# A4989.net
KiCad netlist of a schematic drawn in EAGLE
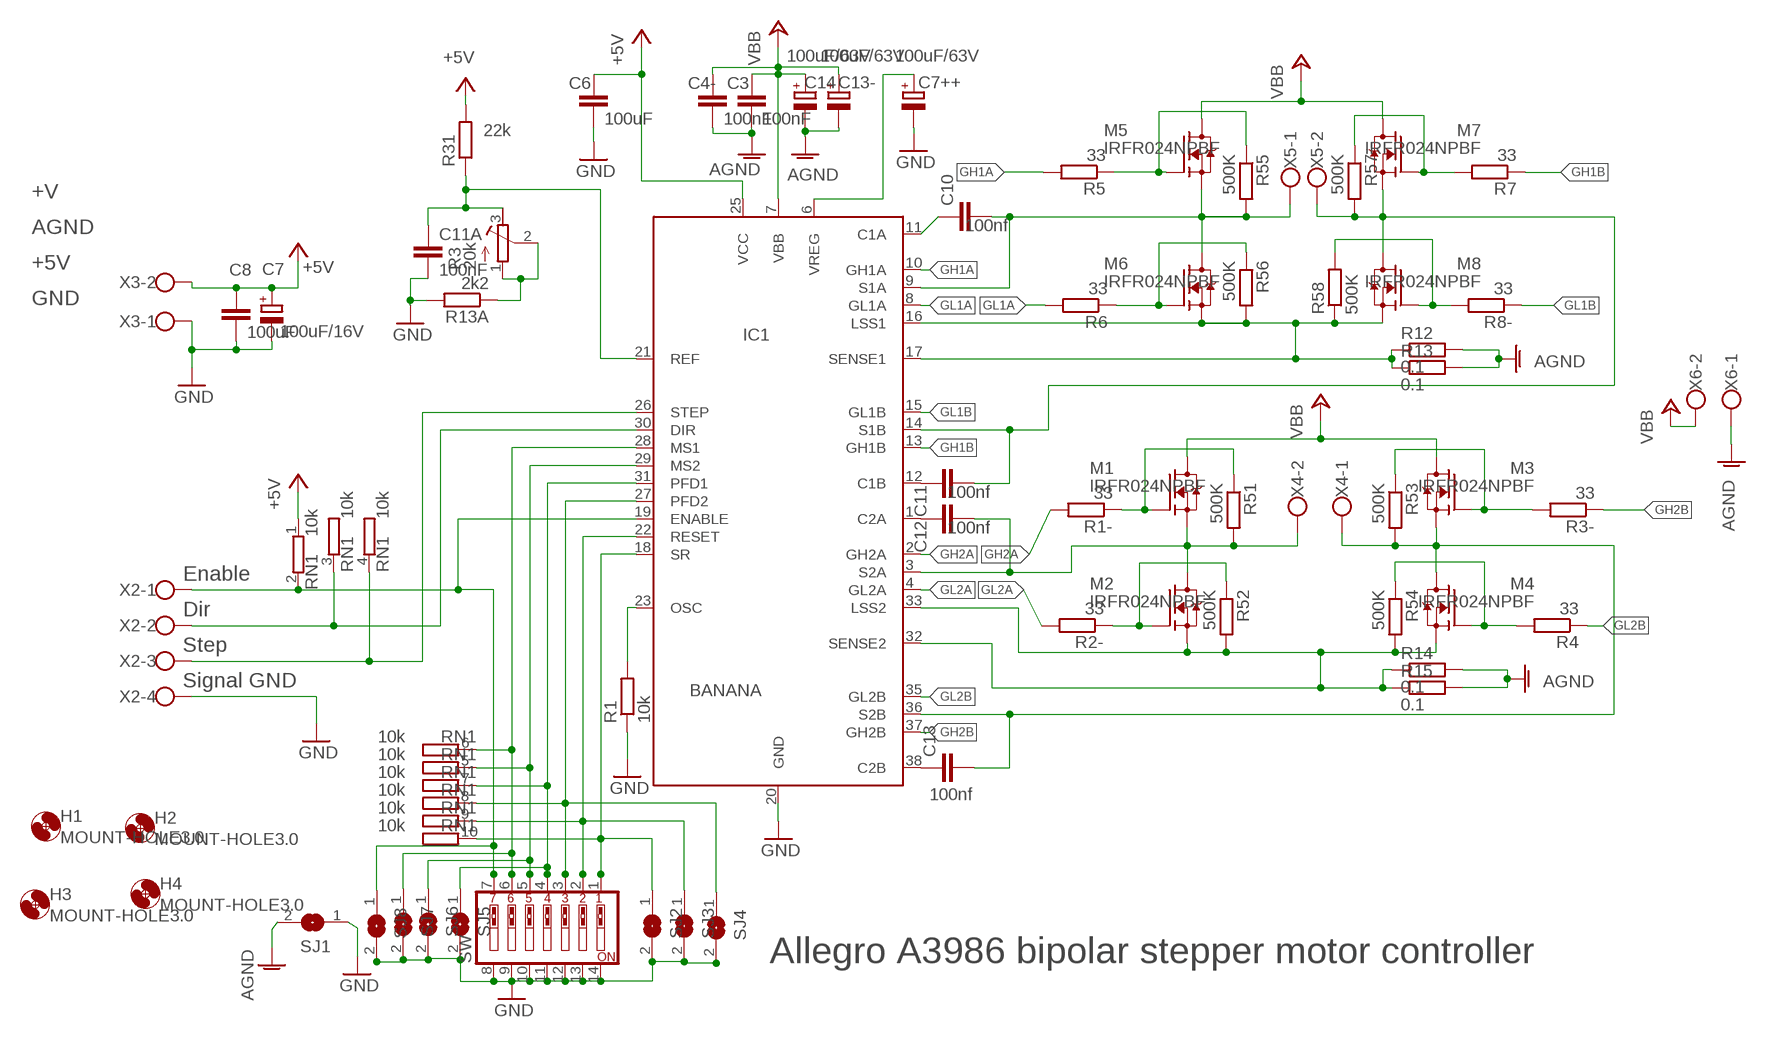
[diagram p0: schematic, sheet 1]

(export (version "E")
  (design (tool "Eeschema 10.0.6"))
  (components
    (comp (ref "C3")
      (value "100nF")
      (footprint "eagle-import:C0805")
      (libsource (lib "eagle-import") (part "C-EUC0805"))
    )
    (comp (ref "C4-")
      (value "100nF")
      (footprint "eagle-import:C0805")
      (libsource (lib "eagle-import") (part "C-EUC0805"))
    )
    (comp (ref "C6")
      (value "100uF")
      (footprint "eagle-import:C0805")
      (libsource (lib "eagle-import") (part "C-EUC0805"))
    )
    (comp (ref "C7")
      (value "100uF/16V")
      (footprint "eagle-import:E5-10,5")
      (libsource (lib "eagle-import") (part "CPOL-EUE5-10.5"))
    )
    (comp (ref "C7++")
      (value "100uF/63V")
      (footprint "eagle-import:E2-5")
      (libsource (lib "eagle-import") (part "resistor_CPOL-EUE2-5"))
    )
    (comp (ref "C8")
      (value "100uF")
      (footprint "eagle-import:C0805")
      (libsource (lib "eagle-import") (part "C-EUC0805"))
    )
    (comp (ref "C10")
      (value "100nf")
      (footprint "eagle-import:C0805")
      (libsource (lib "eagle-import") (part "C-EUC0805"))
    )
    (comp (ref "C11")
      (value "100nf")
      (footprint "eagle-import:C0805")
      (libsource (lib "eagle-import") (part "C-EUC0805"))
    )
    (comp (ref "C11A")
      (value "100nF")
      (footprint "eagle-import:C0805")
      (libsource (lib "eagle-import") (part "C-EUC0805"))
    )
    (comp (ref "C12")
      (value "100nf")
      (footprint "eagle-import:C0805")
      (libsource (lib "eagle-import") (part "C-EUC0805"))
    )
    (comp (ref "C13")
      (value "100nf")
      (footprint "eagle-import:C0805")
      (libsource (lib "eagle-import") (part "C-EUC0805"))
    )
    (comp (ref "C13-")
      (value "100uF/63V")
      (footprint "eagle-import:E5-10,5")
      (libsource (lib "eagle-import") (part "resistor_CPOL-EUE5-10.5"))
    )
    (comp (ref "C14")
      (value "100uF/63V")
      (footprint "eagle-import:E5-10,5")
      (libsource (lib "eagle-import") (part "resistor_CPOL-EUE5-10.5"))
    )
    (comp (ref "H1")
      (value "MOUNT-HOLE3.0")
      (footprint "eagle-import:3,0")
      (libsource (lib "eagle-import") (part "MOUNT-HOLE3.0"))
    )
    (comp (ref "H2")
      (value "MOUNT-HOLE3.0")
      (footprint "eagle-import:3,0")
      (libsource (lib "eagle-import") (part "MOUNT-HOLE3.0"))
    )
    (comp (ref "H3")
      (value "MOUNT-HOLE3.0")
      (footprint "eagle-import:3,0")
      (libsource (lib "eagle-import") (part "MOUNT-HOLE3.0"))
    )
    (comp (ref "H4")
      (value "MOUNT-HOLE3.0")
      (footprint "eagle-import:3,0")
      (libsource (lib "eagle-import") (part "MOUNT-HOLE3.0"))
    )
    (comp (ref "IC1")
      (value "BANANA")
      (footprint "eagle-import:TSSOP38")
      (libsource (lib "eagle-import") (part "A3986"))
    )
    (comp (ref "M1")
      (value "IRFR024NPBF")
      (footprint "eagle-import:DPAK")
      (libsource (lib "eagle-import") (part "IRFR024NPBF"))
    )
    (comp (ref "M2")
      (value "IRFR024NPBF")
      (footprint "eagle-import:DPAK")
      (libsource (lib "eagle-import") (part "IRFR024NPBF"))
    )
    (comp (ref "M3")
      (value "IRFR024NPBF")
      (footprint "eagle-import:DPAK")
      (libsource (lib "eagle-import") (part "IRFR024NPBF"))
    )
    (comp (ref "M4")
      (value "IRFR024NPBF")
      (footprint "eagle-import:DPAK")
      (libsource (lib "eagle-import") (part "IRFR024NPBF"))
    )
    (comp (ref "M5")
      (value "IRFR024NPBF")
      (footprint "eagle-import:DPAK")
      (libsource (lib "eagle-import") (part "IRFR024NPBF"))
    )
    (comp (ref "M6")
      (value "IRFR024NPBF")
      (footprint "eagle-import:DPAK")
      (libsource (lib "eagle-import") (part "IRFR024NPBF"))
    )
    (comp (ref "M7")
      (value "IRFR024NPBF")
      (footprint "eagle-import:DPAK")
      (libsource (lib "eagle-import") (part "IRFR024NPBF"))
    )
    (comp (ref "M8")
      (value "IRFR024NPBF")
      (footprint "eagle-import:DPAK")
      (libsource (lib "eagle-import") (part "IRFR024NPBF"))
    )
    (comp (ref "R1")
      (value "10k")
      (footprint "eagle-import:M0805")
      (libsource (lib "eagle-import") (part "R-EU_M0805"))
    )
    (comp (ref "R1-")
      (value "33")
      (footprint "eagle-import:R0805")
      (libsource (lib "eagle-import") (part "R-EU_R0805"))
    )
    (comp (ref "R2-")
      (value "33")
      (footprint "eagle-import:R0805")
      (libsource (lib "eagle-import") (part "R-EU_R0805"))
    )
    (comp (ref "R3")
      (value "20k")
      (footprint "eagle-import:RTRIM64W")
      (libsource (lib "eagle-import") (part "R-TRIMM64W"))
    )
    (comp (ref "R3-")
      (value "33")
      (footprint "eagle-import:R0805")
      (libsource (lib "eagle-import") (part "R-EU_R0805"))
    )
    (comp (ref "R4")
      (value "33")
      (footprint "eagle-import:R0805")
      (libsource (lib "eagle-import") (part "R-EU_R0805"))
    )
    (comp (ref "R5")
      (value "33")
      (footprint "eagle-import:R0805")
      (libsource (lib "eagle-import") (part "R-EU_R0805"))
    )
    (comp (ref "R6")
      (value "33")
      (footprint "eagle-import:R0805")
      (libsource (lib "eagle-import") (part "R-EU_R0805"))
    )
    (comp (ref "R7")
      (value "33")
      (footprint "eagle-import:R0805")
      (libsource (lib "eagle-import") (part "R-EU_R0805"))
    )
    (comp (ref "R8-")
      (value "33")
      (footprint "eagle-import:R0805")
      (libsource (lib "eagle-import") (part "R-EU_R0805"))
    )
    (comp (ref "R12")
      (value "0.1")
      (footprint "eagle-import:R2512")
      (libsource (lib "eagle-import") (part "R-EU_R2512"))
    )
    (comp (ref "R13")
      (value "0.1")
      (footprint "eagle-import:R2512")
      (libsource (lib "eagle-import") (part "R-EU_R2512"))
    )
    (comp (ref "R13A")
      (value "2k2")
      (footprint "eagle-import:M0805")
      (libsource (lib "eagle-import") (part "R-EU_M0805"))
    )
    (comp (ref "R14")
      (value "0.1")
      (footprint "eagle-import:R2512")
      (libsource (lib "eagle-import") (part "R-EU_R2512"))
    )
    (comp (ref "R15")
      (value "0.1")
      (footprint "eagle-import:R2512")
      (libsource (lib "eagle-import") (part "R-EU_R2512"))
    )
    (comp (ref "R31")
      (value "22k")
      (footprint "eagle-import:M0805")
      (libsource (lib "eagle-import") (part "R-EU_M0805"))
    )
    (comp (ref "R51")
      (value "500K")
      (footprint "eagle-import:R0805")
      (libsource (lib "eagle-import") (part "R-EU_R0805"))
    )
    (comp (ref "R52")
      (value "500K")
      (footprint "eagle-import:R0805")
      (libsource (lib "eagle-import") (part "R-EU_R0805"))
    )
    (comp (ref "R53")
      (value "500K")
      (footprint "eagle-import:R0805")
      (libsource (lib "eagle-import") (part "R-EU_R0805"))
    )
    (comp (ref "R54")
      (value "500K")
      (footprint "eagle-import:R0805")
      (libsource (lib "eagle-import") (part "R-EU_R0805"))
    )
    (comp (ref "R55")
      (value "500K")
      (footprint "eagle-import:R0805")
      (libsource (lib "eagle-import") (part "R-EU_R0805"))
    )
    (comp (ref "R56")
      (value "500K")
      (footprint "eagle-import:R0805")
      (libsource (lib "eagle-import") (part "R-EU_R0805"))
    )
    (comp (ref "R57")
      (value "500K")
      (footprint "eagle-import:R0805")
      (libsource (lib "eagle-import") (part "R-EU_R0805"))
    )
    (comp (ref "R58")
      (value "500K")
      (footprint "eagle-import:R0805")
      (libsource (lib "eagle-import") (part "R-EU_R0805"))
    )
    (comp (ref "RN1")
      (value "10k")
      (footprint "eagle-import:SIL10")
      (libsource (lib "eagle-import") (part "GE09RP"))
    )
    (comp (ref "SJ1") (value "SJ") (footprint "eagle-import:SJ") (libsource (lib "eagle-import") (part "SJ")))
    (comp (ref "SJ2") (value "SJ") (footprint "eagle-import:SJ") (libsource (lib "eagle-import") (part "SJ")))
    (comp (ref "SJ3") (value "SJ") (footprint "eagle-import:SJ") (libsource (lib "eagle-import") (part "SJ")))
    (comp (ref "SJ4") (value "SJ") (footprint "eagle-import:SJ") (libsource (lib "eagle-import") (part "SJ")))
    (comp (ref "SJ5") (value "SJ") (footprint "eagle-import:SJ") (libsource (lib "eagle-import") (part "SJ")))
    (comp (ref "SJ6") (value "SJ") (footprint "eagle-import:SJ") (libsource (lib "eagle-import") (part "SJ")))
    (comp (ref "SJ7") (value "SJ") (footprint "eagle-import:SJ") (libsource (lib "eagle-import") (part "SJ")))
    (comp (ref "SJ8") (value "SJ") (footprint "eagle-import:SJ") (libsource (lib "eagle-import") (part "SJ")))
    (comp (ref "SW")
      (value "SW_DIP-7")
      (footprint "eagle-import:EDG-07")
      (libsource (lib "eagle-import") (part "SW_DIP-7"))
    )
    (comp (ref "X2")
      (value "W237-4")
      (footprint "eagle-import:W237-4")
      (libsource (lib "eagle-import") (part "W237-4"))
    )
    (comp (ref "X3")
      (value "W237-102")
      (footprint "eagle-import:W237-102")
      (fields (field (name "MPN") "237-102"))
      (libsource (lib "eagle-import") (part "W237-102"))
    )
    (comp (ref "X4")
      (value "W237-102")
      (footprint "eagle-import:W237-102")
      (fields (field (name "MPN") "237-102"))
      (libsource (lib "eagle-import") (part "W237-102"))
    )
    (comp (ref "X5")
      (value "W237-102")
      (footprint "eagle-import:W237-102")
      (fields (field (name "MPN") "237-102"))
      (libsource (lib "eagle-import") (part "W237-102"))
    )
    (comp (ref "X6")
      (value "W237-102")
      (footprint "eagle-import:W237-102")
      (fields (field (name "MPN") "237-102"))
      (libsource (lib "eagle-import") (part "W237-102"))
    )
  )
  (nets
    (net (code "1") (name "+5V") (class "Default")
      (node (ref "C6") (pin "1") (pinfunction "1_1") (pintype "passive"))
      (node (ref "C7") (pin "+") (pinfunction "+_+") (pintype "passive"))
      (node (ref "C8") (pin "1") (pinfunction "1_1") (pintype "passive"))
      (node (ref "IC1") (pin "25") (pinfunction "VCC_25") (pintype "passive"))
      (node (ref "R31") (pin "2") (pinfunction "2_2") (pintype "passive"))
      (node (ref "RN1") (pin "1") (pinfunction "1_1") (pintype "passive"))
      (node (ref "X3") (pin "2") (pinfunction "KL_2") (pintype "passive"))
    )
    (net (code "2") (name "AGND") (class "Default")
      (node (ref "C13-") (pin "-") (pinfunction "-_-") (pintype "passive"))
      (node (ref "C14") (pin "-") (pinfunction "-_-") (pintype "passive"))
      (node (ref "C3") (pin "2") (pinfunction "2_2") (pintype "passive"))
      (node (ref "C4-") (pin "2") (pinfunction "2_2") (pintype "passive"))
      (node (ref "R12") (pin "2") (pinfunction "2_2") (pintype "passive"))
      (node (ref "R13") (pin "2") (pinfunction "2_2") (pintype "passive"))
      (node (ref "R14") (pin "2") (pinfunction "2_2") (pintype "passive"))
      (node (ref "R15") (pin "2") (pinfunction "2_2") (pintype "passive"))
      (node (ref "SJ1") (pin "2") (pinfunction "2_2") (pintype "passive"))
      (node (ref "X6") (pin "1") (pinfunction "KL_1") (pintype "passive"))
    )
    (net (code "3") (name "GH1A") (class "Default")
      (node (ref "IC1") (pin "10") (pinfunction "GH1A_10") (pintype "passive"))
      (node (ref "R5") (pin "2") (pinfunction "2_2") (pintype "passive"))
    )
    (net (code "4") (name "GH1B") (class "Default")
      (node (ref "IC1") (pin "13") (pinfunction "GH1B_13") (pintype "passive"))
      (node (ref "R7") (pin "1") (pinfunction "1_1") (pintype "passive"))
    )
    (net (code "5") (name "GH2A") (class "Default")
      (node (ref "IC1") (pin "2") (pinfunction "GH2A_2") (pintype "passive"))
      (node (ref "R1-") (pin "2") (pinfunction "2_2") (pintype "passive"))
    )
    (net (code "6") (name "GH2B") (class "Default")
      (node (ref "IC1") (pin "37") (pinfunction "GH2B_37") (pintype "passive"))
      (node (ref "R3-") (pin "1") (pinfunction "1_1") (pintype "passive"))
    )
    (net (code "7") (name "GL1A") (class "Default")
      (node (ref "IC1") (pin "8") (pinfunction "GL1A_8") (pintype "passive"))
      (node (ref "R6") (pin "2") (pinfunction "2_2") (pintype "passive"))
    )
    (net (code "8") (name "GL1B") (class "Default")
      (node (ref "IC1") (pin "15") (pinfunction "GL1B_15") (pintype "passive"))
      (node (ref "R8-") (pin "1") (pinfunction "1_1") (pintype "passive"))
    )
    (net (code "9") (name "GL2A") (class "Default")
      (node (ref "IC1") (pin "4") (pinfunction "GL2A_4") (pintype "passive"))
      (node (ref "R2-") (pin "2") (pinfunction "2_2") (pintype "passive"))
    )
    (net (code "10") (name "GL2B") (class "Default")
      (node (ref "IC1") (pin "35") (pinfunction "GL2B_35") (pintype "passive"))
      (node (ref "R4") (pin "1") (pinfunction "1_1") (pintype "passive"))
    )
    (net (code "11") (name "GND") (class "Default")
      (node (ref "C11A") (pin "2") (pinfunction "2_2") (pintype "passive"))
      (node (ref "C6") (pin "2") (pinfunction "2_2") (pintype "passive"))
      (node (ref "C7") (pin "-") (pinfunction "-_-") (pintype "passive"))
      (node (ref "C7++") (pin "-") (pinfunction "-_-") (pintype "passive"))
      (node (ref "C8") (pin "2") (pinfunction "2_2") (pintype "passive"))
      (node (ref "IC1") (pin "20") (pinfunction "GND_20") (pintype "passive"))
      (node (ref "R1") (pin "1") (pinfunction "1_1") (pintype "passive"))
      (node (ref "R13A") (pin "2") (pinfunction "2_2") (pintype "passive"))
      (node (ref "SJ1") (pin "1") (pinfunction "1_1") (pintype "passive"))
      (node (ref "SJ2") (pin "2") (pinfunction "2_2") (pintype "passive"))
      (node (ref "SJ3") (pin "2") (pinfunction "2_2") (pintype "passive"))
      (node (ref "SJ4") (pin "2") (pinfunction "2_2") (pintype "passive"))
      (node (ref "SJ5") (pin "2") (pinfunction "2_2") (pintype "passive"))
      (node (ref "SJ6") (pin "2") (pinfunction "2_2") (pintype "passive"))
      (node (ref "SJ7") (pin "2") (pinfunction "2_2") (pintype "passive"))
      (node (ref "SJ8") (pin "2") (pinfunction "2_2") (pintype "passive"))
      (node (ref "SW") (pin "10") (pinfunction "10_10") (pintype "passive"))
      (node (ref "SW") (pin "11") (pinfunction "11_11") (pintype "passive"))
      (node (ref "SW") (pin "12") (pinfunction "12_12") (pintype "passive"))
      (node (ref "SW") (pin "13") (pinfunction "13_13") (pintype "passive"))
      (node (ref "SW") (pin "14") (pinfunction "14_14") (pintype "passive"))
      (node (ref "SW") (pin "8") (pinfunction "8_8") (pintype "passive"))
      (node (ref "SW") (pin "9") (pinfunction "9_9") (pintype "passive"))
      (node (ref "X2") (pin "4") (pinfunction "KL_4") (pintype "passive"))
      (node (ref "X3") (pin "1") (pinfunction "KL_1") (pintype "passive"))
    )
    (net (code "12") (name "Net-(IC1-C1A)") (class "Default")
      (node (ref "C10") (pin "1") (pinfunction "1_1") (pintype "passive"))
      (node (ref "IC1") (pin "11") (pinfunction "C1A_11") (pintype "passive"))
    )
    (net (code "13") (name "Net-(IC1-C1B)") (class "Default")
      (node (ref "C11") (pin "1") (pinfunction "1_1") (pintype "passive"))
      (node (ref "IC1") (pin "12") (pinfunction "C1B_12") (pintype "passive"))
    )
    (net (code "14") (name "Net-(IC1-C2A)") (class "Default")
      (node (ref "C12") (pin "1") (pinfunction "1_1") (pintype "passive"))
      (node (ref "IC1") (pin "1") (pinfunction "C2A_1") (pintype "passive"))
    )
    (net (code "15") (name "Net-(IC1-C2B)") (class "Default")
      (node (ref "C13") (pin "1") (pinfunction "1_1") (pintype "passive"))
      (node (ref "IC1") (pin "38") (pinfunction "C2B_38") (pintype "passive"))
    )
    (net (code "16") (name "Net-(IC1-DIR)") (class "Default")
      (node (ref "IC1") (pin "30") (pinfunction "DIR_30") (pintype "passive"))
      (node (ref "RN1") (pin "3") (pinfunction "2_3") (pintype "passive"))
      (node (ref "X2") (pin "2") (pinfunction "KL_2") (pintype "passive"))
    )
    (net (code "17") (name "Net-(IC1-ENABLE)") (class "Default")
      (node (ref "IC1") (pin "19") (pinfunction "ENABLE_19") (pintype "passive"))
      (node (ref "RN1") (pin "2") (pinfunction "2_2") (pintype "passive"))
      (node (ref "SJ8") (pin "1") (pinfunction "1_1") (pintype "passive"))
      (node (ref "SW") (pin "7") (pinfunction "7_7") (pintype "passive"))
      (node (ref "X2") (pin "1") (pinfunction "KL_1") (pintype "passive"))
    )
    (net (code "18") (name "Net-(IC1-LSS1)") (class "Default")
      (node (ref "IC1") (pin "16") (pinfunction "LSS1_16") (pintype "passive"))
      (node (ref "IC1") (pin "17") (pinfunction "SENSE1_17") (pintype "passive"))
      (node (ref "M6") (pin "3") (pinfunction "S_3") (pintype "passive"))
      (node (ref "M8") (pin "3") (pinfunction "S_3") (pintype "passive"))
      (node (ref "R12") (pin "1") (pinfunction "1_1") (pintype "passive"))
      (node (ref "R13") (pin "1") (pinfunction "1_1") (pintype "passive"))
      (node (ref "R56") (pin "2") (pinfunction "2_2") (pintype "passive"))
      (node (ref "R58") (pin "1") (pinfunction "1_1") (pintype "passive"))
    )
    (net (code "19") (name "Net-(IC1-LSS2)") (class "Default")
      (node (ref "IC1") (pin "32") (pinfunction "SENSE2_32") (pintype "passive"))
      (node (ref "IC1") (pin "33") (pinfunction "LSS2_33") (pintype "passive"))
      (node (ref "M2") (pin "3") (pinfunction "S_3") (pintype "passive"))
      (node (ref "M4") (pin "3") (pinfunction "S_3") (pintype "passive"))
      (node (ref "R14") (pin "1") (pinfunction "1_1") (pintype "passive"))
      (node (ref "R15") (pin "1") (pinfunction "1_1") (pintype "passive"))
      (node (ref "R52") (pin "2") (pinfunction "2_2") (pintype "passive"))
      (node (ref "R54") (pin "2") (pinfunction "2_2") (pintype "passive"))
    )
    (net (code "20") (name "Net-(IC1-MS1)") (class "Default")
      (node (ref "IC1") (pin "28") (pinfunction "MS1_28") (pintype "passive"))
      (node (ref "RN1") (pin "6") (pinfunction "2_6") (pintype "passive"))
      (node (ref "SJ7") (pin "1") (pinfunction "1_1") (pintype "passive"))
      (node (ref "SW") (pin "6") (pinfunction "6_6") (pintype "passive"))
    )
    (net (code "21") (name "Net-(IC1-MS2)") (class "Default")
      (node (ref "IC1") (pin "29") (pinfunction "MS2_29") (pintype "passive"))
      (node (ref "RN1") (pin "5") (pinfunction "2_5") (pintype "passive"))
      (node (ref "SJ6") (pin "1") (pinfunction "1_1") (pintype "passive"))
      (node (ref "SW") (pin "5") (pinfunction "5_5") (pintype "passive"))
    )
    (net (code "22") (name "Net-(IC1-OSC)") (class "Default")
      (node (ref "IC1") (pin "23") (pinfunction "OSC_23") (pintype "passive"))
      (node (ref "R1") (pin "2") (pinfunction "2_2") (pintype "passive"))
    )
    (net (code "23") (name "Net-(IC1-PFD1)") (class "Default")
      (node (ref "IC1") (pin "31") (pinfunction "PFD1_31") (pintype "passive"))
      (node (ref "RN1") (pin "7") (pinfunction "2_7") (pintype "passive"))
      (node (ref "SJ5") (pin "1") (pinfunction "1_1") (pintype "passive"))
      (node (ref "SW") (pin "4") (pinfunction "4_4") (pintype "passive"))
    )
    (net (code "24") (name "Net-(IC1-PFD2)") (class "Default")
      (node (ref "IC1") (pin "27") (pinfunction "PFD2_27") (pintype "passive"))
      (node (ref "RN1") (pin "8") (pinfunction "2_8") (pintype "passive"))
      (node (ref "SJ4") (pin "1") (pinfunction "1_1") (pintype "passive"))
      (node (ref "SW") (pin "3") (pinfunction "3_3") (pintype "passive"))
    )
    (net (code "25") (name "Net-(IC1-REF)") (class "Default")
      (node (ref "C11A") (pin "1") (pinfunction "1_1") (pintype "passive"))
      (node (ref "IC1") (pin "21") (pinfunction "REF_21") (pintype "passive"))
      (node (ref "R3") (pin "3") (pinfunction "A_3") (pintype "passive"))
      (node (ref "R31") (pin "1") (pinfunction "1_1") (pintype "passive"))
    )
    (net (code "26") (name "Net-(IC1-RESET)") (class "Default")
      (node (ref "IC1") (pin "22") (pinfunction "RESET_22") (pintype "passive"))
      (node (ref "RN1") (pin "9") (pinfunction "2_9") (pintype "passive"))
      (node (ref "SJ3") (pin "1") (pinfunction "1_1") (pintype "passive"))
      (node (ref "SW") (pin "2") (pinfunction "2_2") (pintype "passive"))
    )
    (net (code "27") (name "Net-(IC1-S1A)") (class "Default")
      (node (ref "C10") (pin "2") (pinfunction "2_2") (pintype "passive"))
      (node (ref "IC1") (pin "9") (pinfunction "S1A_9") (pintype "passive"))
      (node (ref "M5") (pin "3") (pinfunction "S_3") (pintype "passive"))
      (node (ref "M6") (pin "4") (pinfunction "D_4") (pintype "passive"))
      (node (ref "R55") (pin "2") (pinfunction "2_2") (pintype "passive"))
      (node (ref "X5") (pin "1") (pinfunction "KL_1") (pintype "passive"))
    )
    (net (code "28") (name "Net-(IC1-S1B)") (class "Default")
      (node (ref "C11") (pin "2") (pinfunction "2_2") (pintype "passive"))
      (node (ref "IC1") (pin "14") (pinfunction "S1B_14") (pintype "passive"))
      (node (ref "M7") (pin "3") (pinfunction "S_3") (pintype "passive"))
      (node (ref "M8") (pin "4") (pinfunction "D_4") (pintype "passive"))
      (node (ref "R57") (pin "2") (pinfunction "2_2") (pintype "passive"))
      (node (ref "X5") (pin "2") (pinfunction "KL_2") (pintype "passive"))
    )
    (net (code "29") (name "Net-(IC1-S2A)") (class "Default")
      (node (ref "C12") (pin "2") (pinfunction "2_2") (pintype "passive"))
      (node (ref "IC1") (pin "3") (pinfunction "S2A_3") (pintype "passive"))
      (node (ref "M1") (pin "3") (pinfunction "S_3") (pintype "passive"))
      (node (ref "M2") (pin "4") (pinfunction "D_4") (pintype "passive"))
      (node (ref "R51") (pin "2") (pinfunction "2_2") (pintype "passive"))
      (node (ref "X4") (pin "2") (pinfunction "KL_2") (pintype "passive"))
    )
    (net (code "30") (name "Net-(IC1-S2B)") (class "Default")
      (node (ref "C13") (pin "2") (pinfunction "2_2") (pintype "passive"))
      (node (ref "IC1") (pin "36") (pinfunction "S2B_36") (pintype "passive"))
      (node (ref "M3") (pin "3") (pinfunction "S_3") (pintype "passive"))
      (node (ref "M4") (pin "4") (pinfunction "D_4") (pintype "passive"))
      (node (ref "R53") (pin "2") (pinfunction "2_2") (pintype "passive"))
      (node (ref "X4") (pin "1") (pinfunction "KL_1") (pintype "passive"))
    )
    (net (code "31") (name "Net-(IC1-SR)") (class "Default")
      (node (ref "IC1") (pin "18") (pinfunction "SR_18") (pintype "passive"))
      (node (ref "RN1") (pin "10") (pinfunction "2_10") (pintype "passive"))
      (node (ref "SJ2") (pin "1") (pinfunction "1_1") (pintype "passive"))
      (node (ref "SW") (pin "1") (pinfunction "1_1") (pintype "passive"))
    )
    (net (code "32") (name "Net-(IC1-STEP)") (class "Default")
      (node (ref "IC1") (pin "26") (pinfunction "STEP_26") (pintype "passive"))
      (node (ref "RN1") (pin "4") (pinfunction "2_4") (pintype "passive"))
      (node (ref "X2") (pin "3") (pinfunction "KL_3") (pintype "passive"))
    )
    (net (code "33") (name "Net-(IC1-VREG)") (class "Default")
      (node (ref "C7++") (pin "+") (pinfunction "+_+") (pintype "passive"))
      (node (ref "IC1") (pin "6") (pinfunction "VREG_6") (pintype "passive"))
    )
    (net (code "34") (name "Net-(M1-G)") (class "Default")
      (node (ref "M1") (pin "1") (pinfunction "G_1") (pintype "passive"))
      (node (ref "R1-") (pin "1") (pinfunction "1_1") (pintype "passive"))
      (node (ref "R51") (pin "1") (pinfunction "1_1") (pintype "passive"))
    )
    (net (code "35") (name "Net-(M2-G)") (class "Default")
      (node (ref "M2") (pin "1") (pinfunction "G_1") (pintype "passive"))
      (node (ref "R2-") (pin "1") (pinfunction "1_1") (pintype "passive"))
      (node (ref "R52") (pin "1") (pinfunction "1_1") (pintype "passive"))
    )
    (net (code "36") (name "Net-(M3-G)") (class "Default")
      (node (ref "M3") (pin "1") (pinfunction "G_1") (pintype "passive"))
      (node (ref "R3-") (pin "2") (pinfunction "2_2") (pintype "passive"))
      (node (ref "R53") (pin "1") (pinfunction "1_1") (pintype "passive"))
    )
    (net (code "37") (name "Net-(M4-G)") (class "Default")
      (node (ref "M4") (pin "1") (pinfunction "G_1") (pintype "passive"))
      (node (ref "R4") (pin "2") (pinfunction "2_2") (pintype "passive"))
      (node (ref "R54") (pin "1") (pinfunction "1_1") (pintype "passive"))
    )
    (net (code "38") (name "Net-(M5-G)") (class "Default")
      (node (ref "M5") (pin "1") (pinfunction "G_1") (pintype "passive"))
      (node (ref "R5") (pin "1") (pinfunction "1_1") (pintype "passive"))
      (node (ref "R55") (pin "1") (pinfunction "1_1") (pintype "passive"))
    )
    (net (code "39") (name "Net-(M6-G)") (class "Default")
      (node (ref "M6") (pin "1") (pinfunction "G_1") (pintype "passive"))
      (node (ref "R56") (pin "1") (pinfunction "1_1") (pintype "passive"))
      (node (ref "R6") (pin "1") (pinfunction "1_1") (pintype "passive"))
    )
    (net (code "40") (name "Net-(M7-G)") (class "Default")
      (node (ref "M7") (pin "1") (pinfunction "G_1") (pintype "passive"))
      (node (ref "R57") (pin "1") (pinfunction "1_1") (pintype "passive"))
      (node (ref "R7") (pin "2") (pinfunction "2_2") (pintype "passive"))
    )
    (net (code "41") (name "Net-(M8-G)") (class "Default")
      (node (ref "M8") (pin "1") (pinfunction "G_1") (pintype "passive"))
      (node (ref "R58") (pin "2") (pinfunction "2_2") (pintype "passive"))
      (node (ref "R8-") (pin "2") (pinfunction "2_2") (pintype "passive"))
    )
    (net (code "42") (name "Net-(R3-E)") (class "Default")
      (node (ref "R13A") (pin "1") (pinfunction "1_1") (pintype "passive"))
      (node (ref "R3") (pin "1") (pinfunction "E_1") (pintype "passive"))
      (node (ref "R3") (pin "2") (pinfunction "S_2") (pintype "passive"))
    )
    (net (code "43") (name "VBB") (class "Default")
      (node (ref "C13-") (pin "+") (pinfunction "+_+") (pintype "passive"))
      (node (ref "C14") (pin "+") (pinfunction "+_+") (pintype "passive"))
      (node (ref "C3") (pin "1") (pinfunction "1_1") (pintype "passive"))
      (node (ref "C4-") (pin "1") (pinfunction "1_1") (pintype "passive"))
      (node (ref "IC1") (pin "7") (pinfunction "VBB_7") (pintype "passive"))
      (node (ref "M1") (pin "4") (pinfunction "D_4") (pintype "passive"))
      (node (ref "M3") (pin "4") (pinfunction "D_4") (pintype "passive"))
      (node (ref "M5") (pin "4") (pinfunction "D_4") (pintype "passive"))
      (node (ref "M7") (pin "4") (pinfunction "D_4") (pintype "passive"))
      (node (ref "X6") (pin "2") (pinfunction "KL_2") (pintype "passive"))
    )
  )
)
